# clocker-12b.net
KiCad netlist of a schematic drawn in EAGLE
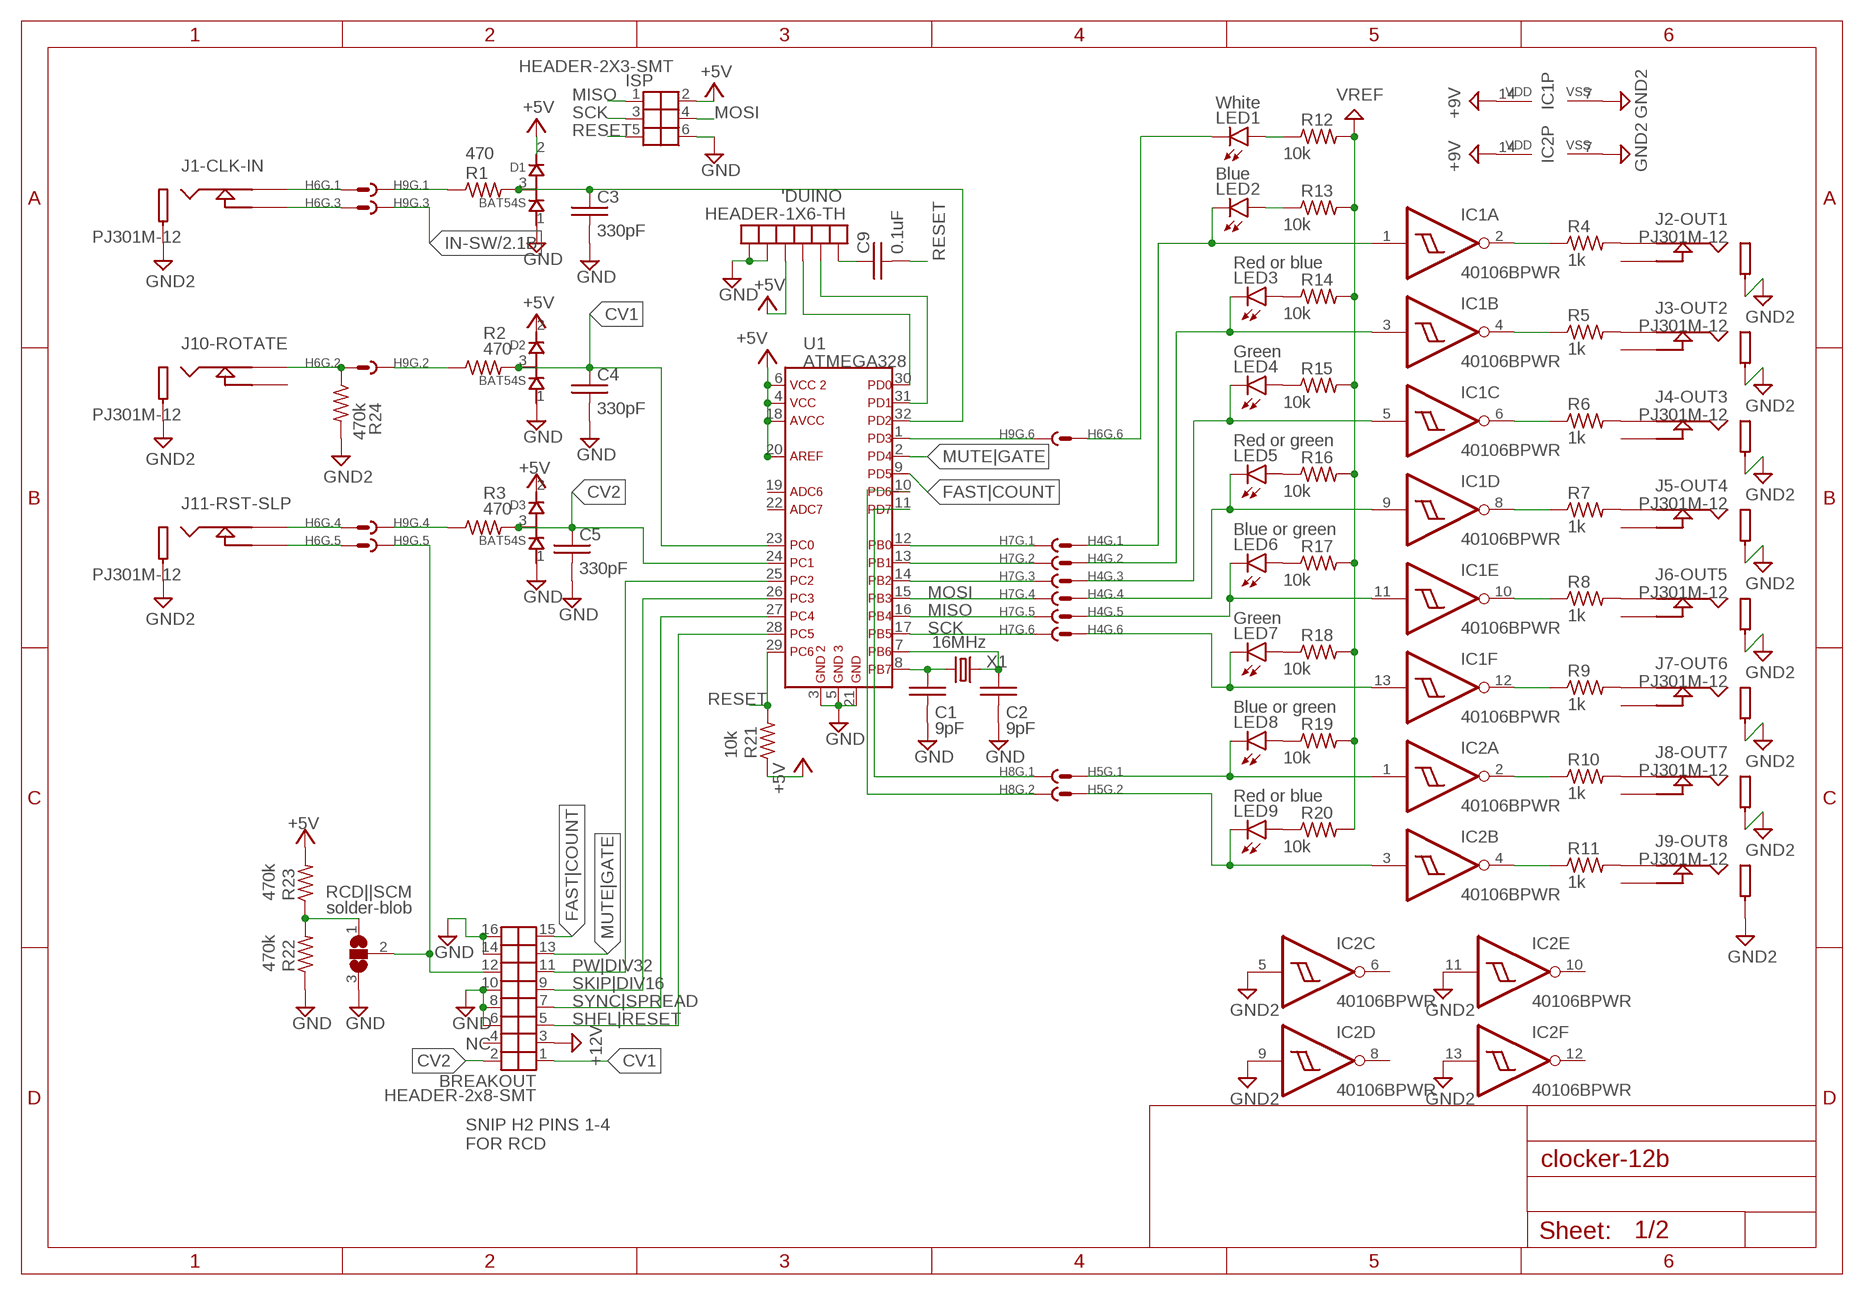
[diagram p0: schematic, sheet 1]
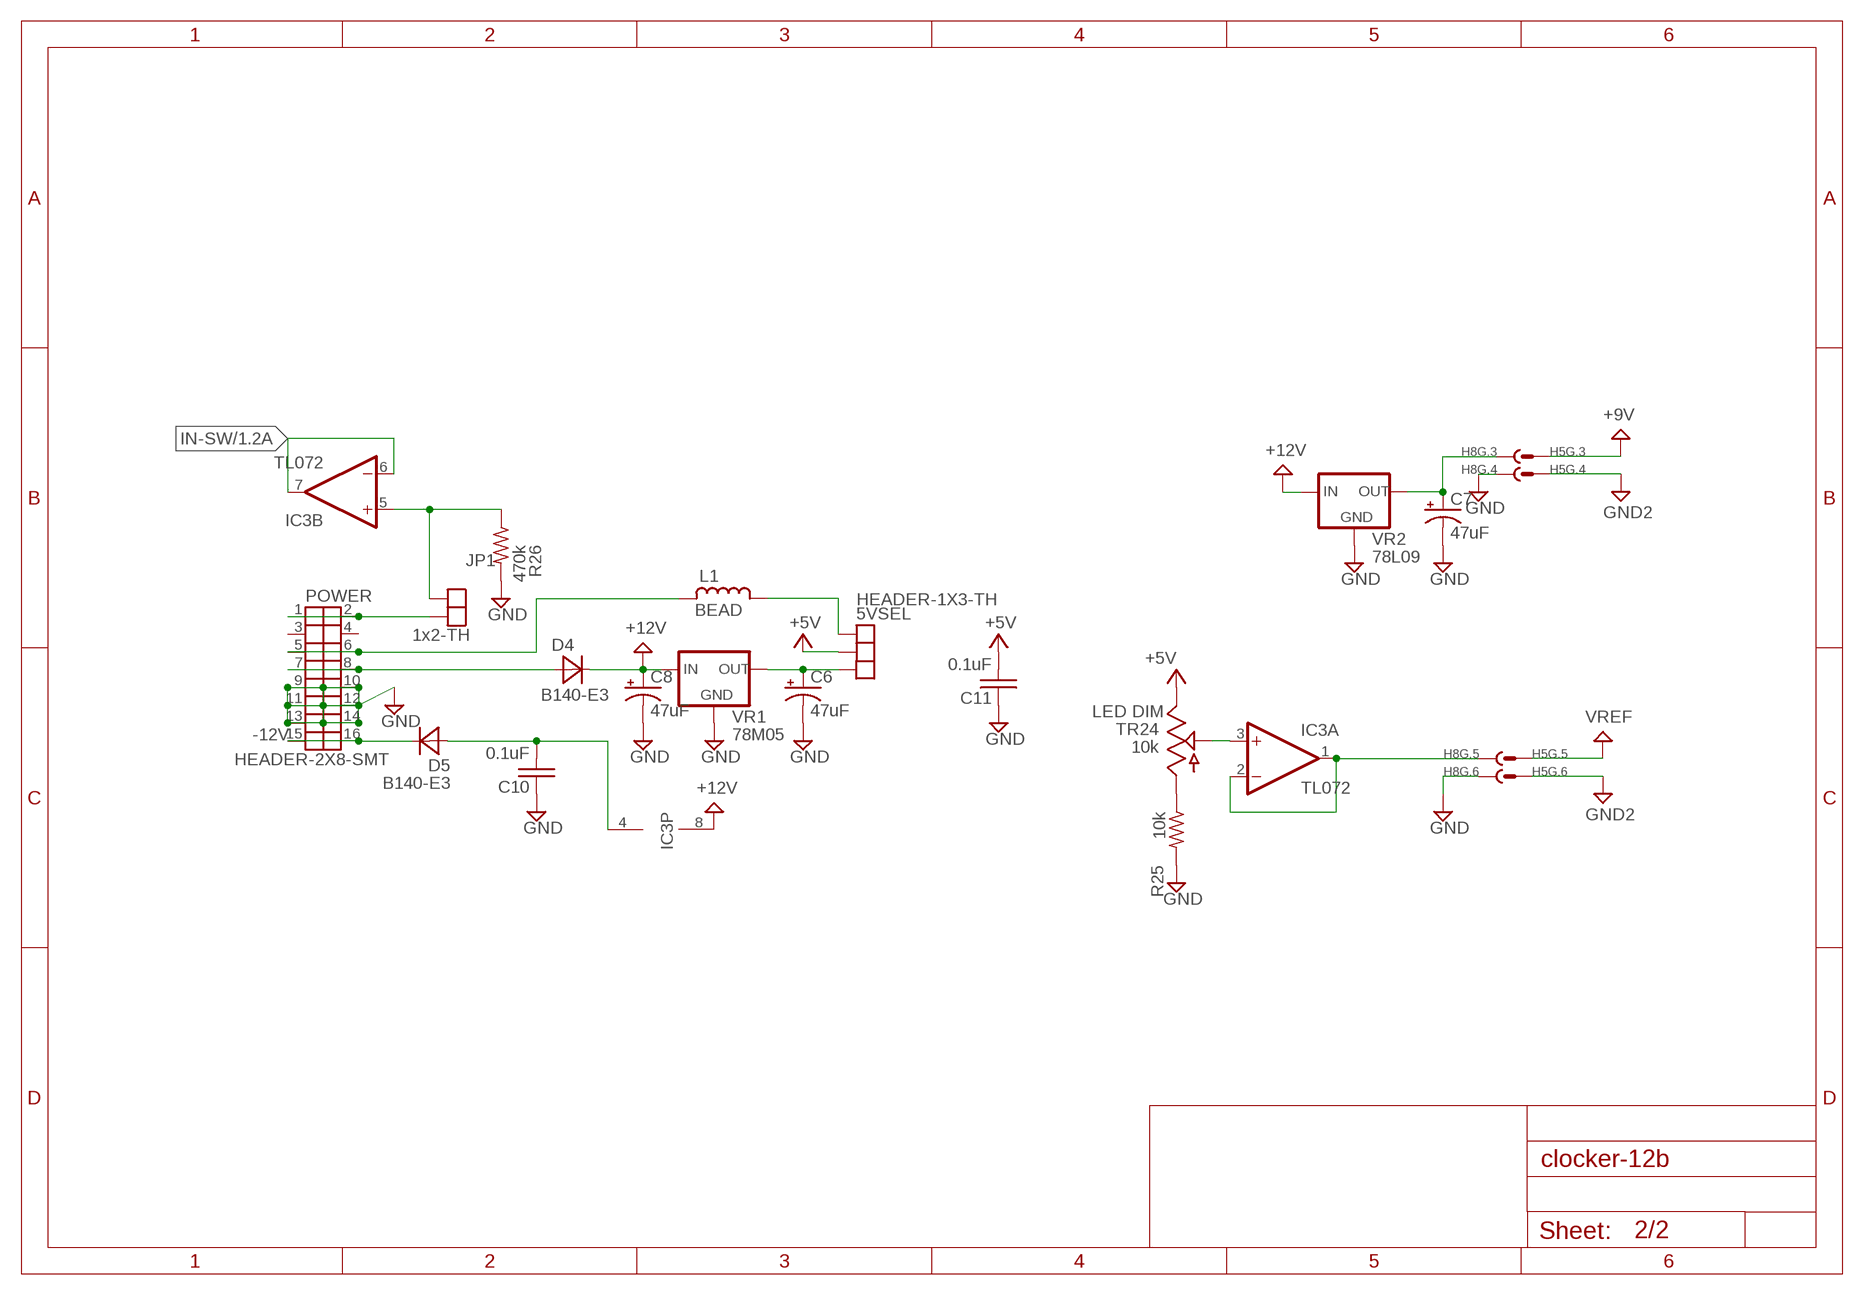
[diagram p1: schematic, sheet 2]

(export (version "E")
  (design (tool "Eeschema 10.0.6"))
  (components
    (comp (ref "5VSEL")
      (value "HEADER-1X3-TH")
      (footprint "eagle-import:HEADER-1X3-TH")
      (libsource (lib "eagle-import") (part "HEADER-1X3"))
    )
    (comp (ref "C6")
      (value "47uF")
      (footprint "eagle-import:C-POL-5")
      (libsource (lib "eagle-import") (part "C-POL5"))
    )
    (comp (ref "C7")
      (value "47uF")
      (footprint "eagle-import:C-POL-5")
      (libsource (lib "eagle-import") (part "C-POL5"))
    )
    (comp (ref "C8")
      (value "47uF")
      (footprint "eagle-import:C-POL-5")
      (libsource (lib "eagle-import") (part "C-POL5"))
    )
    (comp (ref "C10")
      (value "0.1uF")
      (footprint "eagle-import:C0603")
      (libsource (lib "eagle-import") (part "CB"))
    )
    (comp (ref "C11")
      (value "0.1uF")
      (footprint "eagle-import:C0603")
      (libsource (lib "eagle-import") (part "CB"))
    )
    (comp (ref "D4")
      (value "B140-E3")
      (footprint "eagle-import:SMA")
      (libsource (lib "eagle-import") (part "DA"))
    )
    (comp (ref "D5")
      (value "B140-E3")
      (footprint "eagle-import:SMA")
      (libsource (lib "eagle-import") (part "DA"))
    )
    (comp (ref "H5")
      (value "HEADER-2X3-B2B-MALESMT")
      (footprint "eagle-import:HEADER-2X3-SMT")
      (libsource (lib "eagle-import") (part "HEADER-2X3-B2B-MALESMT"))
    )
    (comp (ref "H8")
      (value "HEADER-2X3-B2B-FEMALETH-BOT")
      (footprint "eagle-import:HEADER-2X3-TH-BOTTOM")
      (libsource (lib "eagle-import") (part "HEADER-2X3-B2B-FEMALETH-BOT"))
    )
    (comp (ref "IC3")
      (value "TL072")
      (footprint "eagle-import:SOIC8")
      (libsource (lib "eagle-import") (part "OPAMP-2TL072M"))
    )
    (comp (ref "JP1")
      (value "1x2-TH")
      (footprint "eagle-import:HEADER-1X2-TH")
      (libsource (lib "eagle-import") (part "HEADER-1X2"))
    )
    (comp (ref "L1")
      (value "BEAD")
      (footprint "eagle-import:0603")
      (libsource (lib "eagle-import") (part "LB"))
    )
    (comp (ref "POWER")
      (value "HEADER-2X8-SMT")
      (footprint "eagle-import:HEADER-2X8-SMT-SHROUDED")
      (libsource (lib "eagle-import") (part "HEADER-2X8SHRD"))
    )
    (comp (ref "R25")
      (value "10k")
      (footprint "eagle-import:R0603")
      (libsource (lib "eagle-import") (part "RB"))
    )
    (comp (ref "R26")
      (value "470k")
      (footprint "eagle-import:R0603")
      (libsource (lib "eagle-import") (part "RB"))
    )
    (comp (ref "TR24")
      (value "10k")
      (footprint "eagle-import:PIHER-6MM")
      (fields (field (name "USE") "LED DIM"))
      (libsource (lib "eagle-import") (part "POT-MI"))
    )
    (comp (ref "VR1")
      (value "78M05")
      (footprint "eagle-import:DPAK")
      (libsource (lib "eagle-import") (part "VREG-POS78A"))
    )
    (comp (ref "VR2")
      (value "78L09")
      (footprint "eagle-import:SOT89")
      (libsource (lib "eagle-import") (part "VREG-POS78R"))
    )
    (comp (ref "'DUINO")
      (value "HEADER-1X6-TH")
      (footprint "eagle-import:HEADER-1X6-TH")
      (libsource (lib "eagle-import") (part "HEADER-1X6"))
    )
    (comp (ref "BREAKOUT")
      (value "HEADER-2x8-SMT")
      (footprint "eagle-import:HEADER-2X8-SMT")
      (libsource (lib "eagle-import") (part "HEADER-2X8BARE"))
    )
    (comp (ref "C1")
      (value "9pF")
      (footprint "eagle-import:C0603")
      (libsource (lib "eagle-import") (part "CB"))
    )
    (comp (ref "C2")
      (value "9pF")
      (footprint "eagle-import:C0603")
      (libsource (lib "eagle-import") (part "CB"))
    )
    (comp (ref "C3")
      (value "330pF")
      (footprint "eagle-import:C0603")
      (libsource (lib "eagle-import") (part "CB"))
    )
    (comp (ref "C4")
      (value "330pF")
      (footprint "eagle-import:C0603")
      (libsource (lib "eagle-import") (part "CB"))
    )
    (comp (ref "C5")
      (value "330pF")
      (footprint "eagle-import:C0603")
      (libsource (lib "eagle-import") (part "CB"))
    )
    (comp (ref "C9")
      (value "0.1uF")
      (footprint "eagle-import:C0603")
      (libsource (lib "eagle-import") (part "CB"))
    )
    (comp (ref "D1")
      (value "BAT54S")
      (footprint "eagle-import:SOT23")
      (libsource (lib "eagle-import") (part "DIODE-DUAL"))
    )
    (comp (ref "D2")
      (value "BAT54S")
      (footprint "eagle-import:SOT23")
      (libsource (lib "eagle-import") (part "DIODE-DUAL"))
    )
    (comp (ref "D3")
      (value "BAT54S")
      (footprint "eagle-import:SOT23")
      (libsource (lib "eagle-import") (part "DIODE-DUAL"))
    )
    (comp (ref "H4")
      (value "HEADER-2X3-B2B-MALESMT")
      (footprint "eagle-import:HEADER-2X3-SMT")
      (libsource (lib "eagle-import") (part "HEADER-2X3-B2B-MALESMT"))
    )
    (comp (ref "H6")
      (value "HEADER-2X3-B2B-MALESMT")
      (footprint "eagle-import:HEADER-2X3-SMT")
      (libsource (lib "eagle-import") (part "HEADER-2X3-B2B-MALESMT"))
    )
    (comp (ref "H7")
      (value "HEADER-2X3-B2B-FEMALETH-BOT")
      (footprint "eagle-import:HEADER-2X3-TH-BOTTOM")
      (libsource (lib "eagle-import") (part "HEADER-2X3-B2B-FEMALETH-BOT"))
    )
    (comp (ref "H9")
      (value "HEADER-2X3-B2B-FEMALETH-BOT")
      (footprint "eagle-import:HEADER-2X3-TH-BOTTOM")
      (libsource (lib "eagle-import") (part "HEADER-2X3-B2B-FEMALETH-BOT"))
    )
    (comp (ref "IC1")
      (value "40106BPWR")
      (footprint "eagle-import:TSSOP14")
      (libsource (lib "eagle-import") (part "40106BPWR"))
    )
    (comp (ref "IC2")
      (value "40106BPWR")
      (footprint "eagle-import:TSSOP14")
      (libsource (lib "eagle-import") (part "40106BPWR"))
    )
    (comp (ref "ISP")
      (value "HEADER-2X3-SMT")
      (footprint "eagle-import:HEADER-2X3-SMT")
      (libsource (lib "eagle-import") (part "HEADER-2X3"))
    )
    (comp (ref "J1-CLK-IN")
      (value "PJ301M-12")
      (footprint "eagle-import:PJ301M-12")
      (libsource (lib "eagle-import") (part "JACK-MONO-SWM"))
    )
    (comp (ref "J2-OUT1")
      (value "PJ301M-12")
      (footprint "eagle-import:PJ301M-12")
      (libsource (lib "eagle-import") (part "JACK-MONO-SWM"))
    )
    (comp (ref "J3-OUT2")
      (value "PJ301M-12")
      (footprint "eagle-import:PJ301M-12")
      (libsource (lib "eagle-import") (part "JACK-MONO-SWM"))
    )
    (comp (ref "J4-OUT3")
      (value "PJ301M-12")
      (footprint "eagle-import:PJ301M-12")
      (libsource (lib "eagle-import") (part "JACK-MONO-SWM"))
    )
    (comp (ref "J5-OUT4")
      (value "PJ301M-12")
      (footprint "eagle-import:PJ301M-12")
      (libsource (lib "eagle-import") (part "JACK-MONO-SWM"))
    )
    (comp (ref "J6-OUT5")
      (value "PJ301M-12")
      (footprint "eagle-import:PJ301M-12")
      (libsource (lib "eagle-import") (part "JACK-MONO-SWM"))
    )
    (comp (ref "J7-OUT6")
      (value "PJ301M-12")
      (footprint "eagle-import:PJ301M-12")
      (libsource (lib "eagle-import") (part "JACK-MONO-SWM"))
    )
    (comp (ref "J8-OUT7")
      (value "PJ301M-12")
      (footprint "eagle-import:PJ301M-12")
      (libsource (lib "eagle-import") (part "JACK-MONO-SWM"))
    )
    (comp (ref "J9-OUT8")
      (value "PJ301M-12")
      (footprint "eagle-import:PJ301M-12")
      (libsource (lib "eagle-import") (part "JACK-MONO-SWM"))
    )
    (comp (ref "J10-ROTATE")
      (value "PJ301M-12")
      (footprint "eagle-import:PJ301M-12")
      (libsource (lib "eagle-import") (part "JACK-MONO-SWM"))
    )
    (comp (ref "J11-RST-SLP")
      (value "PJ301M-12")
      (footprint "eagle-import:PJ301M-12")
      (libsource (lib "eagle-import") (part "JACK-MONO-SWM"))
    )
    (comp (ref "LED1")
      (value "White")
      (footprint "eagle-import:LED-T1")
      (libsource (lib "eagle-import") (part "LED"))
    )
    (comp (ref "LED2")
      (value "Blue")
      (footprint "eagle-import:LED-T1")
      (libsource (lib "eagle-import") (part "LED"))
    )
    (comp (ref "LED3")
      (value "Red or blue")
      (footprint "eagle-import:LED-T1")
      (libsource (lib "eagle-import") (part "LED"))
    )
    (comp (ref "LED4")
      (value "Green")
      (footprint "eagle-import:LED-T1")
      (libsource (lib "eagle-import") (part "LED"))
    )
    (comp (ref "LED5")
      (value "Red or green")
      (footprint "eagle-import:LED-T1")
      (libsource (lib "eagle-import") (part "LED"))
    )
    (comp (ref "LED6")
      (value "Blue or green")
      (footprint "eagle-import:LED-T1")
      (libsource (lib "eagle-import") (part "LED"))
    )
    (comp (ref "LED7")
      (value "Green")
      (footprint "eagle-import:LED-T1")
      (libsource (lib "eagle-import") (part "LED"))
    )
    (comp (ref "LED8")
      (value "Blue or green")
      (footprint "eagle-import:LED-T1")
      (libsource (lib "eagle-import") (part "LED"))
    )
    (comp (ref "LED9")
      (value "Red or blue")
      (footprint "eagle-import:LED-T1")
      (libsource (lib "eagle-import") (part "LED"))
    )
    (comp (ref "R1")
      (value "470")
      (footprint "eagle-import:R0603")
      (libsource (lib "eagle-import") (part "RB"))
    )
    (comp (ref "R2")
      (value "470")
      (footprint "eagle-import:R0603")
      (libsource (lib "eagle-import") (part "RB"))
    )
    (comp (ref "R3")
      (value "470")
      (footprint "eagle-import:R0603")
      (libsource (lib "eagle-import") (part "RB"))
    )
    (comp (ref "R4")
      (value "1k")
      (footprint "eagle-import:R0603")
      (libsource (lib "eagle-import") (part "RB"))
    )
    (comp (ref "R5")
      (value "1k")
      (footprint "eagle-import:R0603")
      (libsource (lib "eagle-import") (part "RB"))
    )
    (comp (ref "R6")
      (value "1k")
      (footprint "eagle-import:R0603")
      (libsource (lib "eagle-import") (part "RB"))
    )
    (comp (ref "R7")
      (value "1k")
      (footprint "eagle-import:R0603")
      (libsource (lib "eagle-import") (part "RB"))
    )
    (comp (ref "R8")
      (value "1k")
      (footprint "eagle-import:R0603")
      (libsource (lib "eagle-import") (part "RB"))
    )
    (comp (ref "R9")
      (value "1k")
      (footprint "eagle-import:R0603")
      (libsource (lib "eagle-import") (part "RB"))
    )
    (comp (ref "R10")
      (value "1k")
      (footprint "eagle-import:R0603")
      (libsource (lib "eagle-import") (part "RB"))
    )
    (comp (ref "R11")
      (value "1k")
      (footprint "eagle-import:R0603")
      (libsource (lib "eagle-import") (part "RB"))
    )
    (comp (ref "R12")
      (value "10k")
      (footprint "eagle-import:R0603")
      (libsource (lib "eagle-import") (part "RB"))
    )
    (comp (ref "R13")
      (value "10k")
      (footprint "eagle-import:R0603")
      (libsource (lib "eagle-import") (part "RB"))
    )
    (comp (ref "R14")
      (value "10k")
      (footprint "eagle-import:R0603")
      (libsource (lib "eagle-import") (part "RB"))
    )
    (comp (ref "R15")
      (value "10k")
      (footprint "eagle-import:R0603")
      (libsource (lib "eagle-import") (part "RB"))
    )
    (comp (ref "R16")
      (value "10k")
      (footprint "eagle-import:R0603")
      (libsource (lib "eagle-import") (part "RB"))
    )
    (comp (ref "R17")
      (value "10k")
      (footprint "eagle-import:R0603")
      (libsource (lib "eagle-import") (part "RB"))
    )
    (comp (ref "R18")
      (value "10k")
      (footprint "eagle-import:R0603")
      (libsource (lib "eagle-import") (part "RB"))
    )
    (comp (ref "R19")
      (value "10k")
      (footprint "eagle-import:R0603")
      (libsource (lib "eagle-import") (part "RB"))
    )
    (comp (ref "R20")
      (value "10k")
      (footprint "eagle-import:R0603")
      (libsource (lib "eagle-import") (part "RB"))
    )
    (comp (ref "R21")
      (value "10k")
      (footprint "eagle-import:R0603")
      (libsource (lib "eagle-import") (part "RB"))
    )
    (comp (ref "R22")
      (value "470k")
      (footprint "eagle-import:R0603")
      (libsource (lib "eagle-import") (part "RB"))
    )
    (comp (ref "R23")
      (value "470k")
      (footprint "eagle-import:R0603")
      (libsource (lib "eagle-import") (part "RB"))
    )
    (comp (ref "R24")
      (value "470k")
      (footprint "eagle-import:R0603")
      (libsource (lib "eagle-import") (part "RB"))
    )
    (comp (ref "RCD||SCM")
      (value "solder-blob")
      (footprint "eagle-import:SJ_2")
      (libsource (lib "eagle-import") (part "SJ2W"))
    )
    (comp (ref "U1")
      (value "ATMEGA328")
      (footprint "eagle-import:TQFP-32")
      (libsource (lib "eagle-import") (part "ATMEGA168"))
    )
    (comp (ref "X1")
      (value "16MHz")
      (footprint "eagle-import:FA-238")
      (libsource (lib "eagle-import") (part "CRYSTALE"))
    )
  )
  (nets
    (net (code "1") (name "+5V") (class "Default")
      (node (ref "'DUINO") (pin "P$3") (pinfunction "P$3_P$3") (pintype "bidirectional"))
      (node (ref "5VSEL") (pin "P$2") (pinfunction "P$2_P$2") (pintype "bidirectional"))
      (node (ref "C11") (pin "2") (pinfunction "2_2") (pintype "passive"))
      (node (ref "D1") (pin "2") (pinfunction "CATHODE_2") (pintype "bidirectional"))
      (node (ref "D2") (pin "2") (pinfunction "CATHODE_2") (pintype "bidirectional"))
      (node (ref "D3") (pin "2") (pinfunction "CATHODE_2") (pintype "bidirectional"))
      (node (ref "ISP") (pin "2") (pinfunction "P$2_2") (pintype "bidirectional"))
      (node (ref "R21") (pin "1") (pinfunction "1_1") (pintype "passive"))
      (node (ref "R23") (pin "2") (pinfunction "2_2") (pintype "passive"))
      (node (ref "TR24") (pin "3") (pinfunction "3_3") (pintype "passive"))
      (node (ref "U1") (pin "18") (pinfunction "P$18_18") (pintype "passive"))
      (node (ref "U1") (pin "20") (pinfunction "P$20_20") (pintype "passive"))
      (node (ref "U1") (pin "4") (pinfunction "P$4_4") (pintype "passive"))
      (node (ref "U1") (pin "6") (pinfunction "P$6_6") (pintype "passive"))
    )
    (net (code "2") (name "+9V") (class "Default")
      (node (ref "H5") (pin "3") (pinfunction "S_3") (pintype "passive"))
      (node (ref "IC1") (pin "14") (pinfunction "VDD_14") (pintype "power_in"))
      (node (ref "IC2") (pin "14") (pinfunction "VDD_14") (pintype "power_in"))
    )
    (net (code "3") (name "+12V") (class "Default")
      (node (ref "BREAKOUT") (pin "3") (pinfunction "P$3_3") (pintype "bidirectional"))
      (node (ref "C8") (pin "+") (pinfunction "+_+") (pintype "passive"))
      (node (ref "D4") (pin "K") (pinfunction "C_K") (pintype "passive"))
      (node (ref "IC3") (pin "8") (pinfunction "V+_8") (pintype "power_in"))
      (node (ref "VR1") (pin "1") (pinfunction "IN_1") (pintype "input"))
      (node (ref "VR2") (pin "3") (pinfunction "IN_3") (pintype "input"))
    )
    (net (code "4") (name "+VREF") (class "Default")
      (node (ref "H5") (pin "5") (pinfunction "S_5") (pintype "passive"))
      (node (ref "R12") (pin "2") (pinfunction "2_2") (pintype "passive"))
      (node (ref "R13") (pin "2") (pinfunction "2_2") (pintype "passive"))
      (node (ref "R14") (pin "2") (pinfunction "2_2") (pintype "passive"))
      (node (ref "R15") (pin "2") (pinfunction "2_2") (pintype "passive"))
      (node (ref "R16") (pin "2") (pinfunction "2_2") (pintype "passive"))
      (node (ref "R17") (pin "2") (pinfunction "2_2") (pintype "passive"))
      (node (ref "R18") (pin "2") (pinfunction "2_2") (pintype "passive"))
      (node (ref "R19") (pin "2") (pinfunction "2_2") (pintype "passive"))
      (node (ref "R20") (pin "2") (pinfunction "2_2") (pintype "passive"))
    )
    (net (code "5") (name "-12V") (class "Default")
      (node (ref "D5") (pin "K") (pinfunction "C_K") (pintype "passive"))
      (node (ref "POWER") (pin "15") (pinfunction "P$15_15") (pintype "bidirectional"))
      (node (ref "POWER") (pin "16") (pinfunction "P$16_16") (pintype "bidirectional"))
    )
    (net (code "6") (name "AGND") (class "Default")
      (node (ref "H5") (pin "4") (pinfunction "S_4") (pintype "passive"))
      (node (ref "H5") (pin "6") (pinfunction "S_6") (pintype "passive"))
      (node (ref "IC1") (pin "7") (pinfunction "VSS_7") (pintype "power_in"))
      (node (ref "IC2") (pin "11") (pinfunction "I_11") (pintype "input"))
      (node (ref "IC2") (pin "13") (pinfunction "I_13") (pintype "input"))
      (node (ref "IC2") (pin "5") (pinfunction "I_5") (pintype "input"))
      (node (ref "IC2") (pin "7") (pinfunction "VSS_7") (pintype "power_in"))
      (node (ref "IC2") (pin "9") (pinfunction "I_9") (pintype "input"))
      (node (ref "J1-CLK-IN") (pin "2") (pinfunction "SLEEVE_2") (pintype "passive"))
      (node (ref "J10-ROTATE") (pin "2") (pinfunction "SLEEVE_2") (pintype "passive"))
      (node (ref "J11-RST-SLP") (pin "2") (pinfunction "SLEEVE_2") (pintype "passive"))
      (node (ref "J2-OUT1") (pin "2") (pinfunction "SLEEVE_2") (pintype "passive"))
      (node (ref "J3-OUT2") (pin "2") (pinfunction "SLEEVE_2") (pintype "passive"))
      (node (ref "J4-OUT3") (pin "2") (pinfunction "SLEEVE_2") (pintype "passive"))
      (node (ref "J5-OUT4") (pin "2") (pinfunction "SLEEVE_2") (pintype "passive"))
      (node (ref "J6-OUT5") (pin "2") (pinfunction "SLEEVE_2") (pintype "passive"))
      (node (ref "J7-OUT6") (pin "2") (pinfunction "SLEEVE_2") (pintype "passive"))
      (node (ref "J8-OUT7") (pin "2") (pinfunction "SLEEVE_2") (pintype "passive"))
      (node (ref "J9-OUT8") (pin "2") (pinfunction "SLEEVE_2") (pintype "passive"))
      (node (ref "R24") (pin "2") (pinfunction "2_2") (pintype "passive"))
    )
    (net (code "7") (name "CV1") (class "Default")
      (node (ref "BREAKOUT") (pin "1") (pinfunction "P$1_1") (pintype "bidirectional"))
      (node (ref "C4") (pin "1") (pinfunction "1_1") (pintype "passive"))
      (node (ref "D2") (pin "3") (pinfunction "COMMON_3") (pintype "bidirectional"))
      (node (ref "R2") (pin "2") (pinfunction "2_2") (pintype "passive"))
      (node (ref "U1") (pin "23") (pinfunction "P$23_23") (pintype "passive"))
    )
    (net (code "8") (name "CV2") (class "Default")
      (node (ref "BREAKOUT") (pin "2") (pinfunction "P$2_2") (pintype "bidirectional"))
      (node (ref "C5") (pin "1") (pinfunction "1_1") (pintype "passive"))
      (node (ref "D3") (pin "3") (pinfunction "COMMON_3") (pintype "bidirectional"))
      (node (ref "R3") (pin "2") (pinfunction "2_2") (pintype "passive"))
      (node (ref "U1") (pin "24") (pinfunction "P$24_24") (pintype "passive"))
    )
    (net (code "9") (name "FAST|COUNT") (class "Default")
      (node (ref "BREAKOUT") (pin "15") (pinfunction "P$15_15") (pintype "bidirectional"))
      (node (ref "U1") (pin "9") (pinfunction "P$9_9") (pintype "passive"))
    )
    (net (code "10") (name "GND") (class "Default")
      (node (ref "'DUINO") (pin "P$1") (pinfunction "P$1_P$1") (pintype "bidirectional"))
      (node (ref "'DUINO") (pin "P$2") (pinfunction "P$2_P$2") (pintype "bidirectional"))
      (node (ref "BREAKOUT") (pin "10") (pinfunction "P$10_10") (pintype "bidirectional"))
      (node (ref "BREAKOUT") (pin "14") (pinfunction "P$14_14") (pintype "bidirectional"))
      (node (ref "BREAKOUT") (pin "16") (pinfunction "P$16_16") (pintype "bidirectional"))
      (node (ref "BREAKOUT") (pin "6") (pinfunction "P$6_6") (pintype "bidirectional"))
      (node (ref "BREAKOUT") (pin "8") (pinfunction "P$8_8") (pintype "bidirectional"))
      (node (ref "C1") (pin "2") (pinfunction "2_2") (pintype "passive"))
      (node (ref "C10") (pin "1") (pinfunction "1_1") (pintype "passive"))
      (node (ref "C11") (pin "1") (pinfunction "1_1") (pintype "passive"))
      (node (ref "C2") (pin "2") (pinfunction "2_2") (pintype "passive"))
      (node (ref "C3") (pin "2") (pinfunction "2_2") (pintype "passive"))
      (node (ref "C4") (pin "2") (pinfunction "2_2") (pintype "passive"))
      (node (ref "C5") (pin "2") (pinfunction "2_2") (pintype "passive"))
      (node (ref "C6") (pin "-") (pinfunction "-_-") (pintype "passive"))
      (node (ref "C7") (pin "-") (pinfunction "-_-") (pintype "passive"))
      (node (ref "C8") (pin "-") (pinfunction "-_-") (pintype "passive"))
      (node (ref "D1") (pin "1") (pinfunction "ANODE_1") (pintype "bidirectional"))
      (node (ref "D2") (pin "1") (pinfunction "ANODE_1") (pintype "bidirectional"))
      (node (ref "D3") (pin "1") (pinfunction "ANODE_1") (pintype "bidirectional"))
      (node (ref "H8") (pin "P$4") (pinfunction "B_P$4") (pintype "passive"))
      (node (ref "H8") (pin "P$6") (pinfunction "B_P$6") (pintype "passive"))
      (node (ref "ISP") (pin "6") (pinfunction "P$6_6") (pintype "bidirectional"))
      (node (ref "POWER") (pin "10") (pinfunction "P$10_10") (pintype "bidirectional"))
      (node (ref "POWER") (pin "11") (pinfunction "P$11_11") (pintype "bidirectional"))
      (node (ref "POWER") (pin "12") (pinfunction "P$12_12") (pintype "bidirectional"))
      (node (ref "POWER") (pin "13") (pinfunction "P$13_13") (pintype "bidirectional"))
      (node (ref "POWER") (pin "14") (pinfunction "P$14_14") (pintype "bidirectional"))
      (node (ref "POWER") (pin "9") (pinfunction "P$9_9") (pintype "bidirectional"))
      (node (ref "R22") (pin "1") (pinfunction "1_1") (pintype "passive"))
      (node (ref "R25") (pin "2") (pinfunction "2_2") (pintype "passive"))
      (node (ref "R26") (pin "2") (pinfunction "2_2") (pintype "passive"))
      (node (ref "RCD||SCM") (pin "3") (pinfunction "3_3") (pintype "passive"))
      (node (ref "U1") (pin "21") (pinfunction "P$21_21") (pintype "passive"))
      (node (ref "U1") (pin "3") (pinfunction "P$3_3") (pintype "passive"))
      (node (ref "U1") (pin "5") (pinfunction "P$5_5") (pintype "passive"))
      (node (ref "VR1") (pin "4") (pinfunction "GND_4") (pintype "input"))
      (node (ref "VR2") (pin "2A") (pinfunction "GND_2A") (pintype "input"))
      (node (ref "VR2") (pin "2B") (pinfunction "GND_2B") (pintype "input"))
    )
    (net (code "11") (name "IN-SW") (class "Default")
      (node (ref "H9") (pin "P$3") (pinfunction "B_P$3") (pintype "passive"))
      (node (ref "IC3") (pin "6") (pinfunction "-IN_6") (pintype "input"))
      (node (ref "IC3") (pin "7") (pinfunction "OUT_7") (pintype "output"))
    )
    (net (code "12") (name "MISO") (class "Default")
      (node (ref "H7") (pin "P$5") (pinfunction "B_P$5") (pintype "passive"))
      (node (ref "ISP") (pin "1") (pinfunction "P$1_1") (pintype "bidirectional"))
      (node (ref "U1") (pin "16") (pinfunction "P$16_16") (pintype "passive"))
    )
    (net (code "13") (name "MOSI") (class "Default")
      (node (ref "H7") (pin "P$4") (pinfunction "B_P$4") (pintype "passive"))
      (node (ref "ISP") (pin "4") (pinfunction "P$4_4") (pintype "bidirectional"))
      (node (ref "U1") (pin "15") (pinfunction "P$15_15") (pintype "passive"))
    )
    (net (code "14") (name "MUTE|GATE") (class "Default")
      (node (ref "BREAKOUT") (pin "13") (pinfunction "P$13_13") (pintype "bidirectional"))
      (node (ref "U1") (pin "2") (pinfunction "P$2_2") (pintype "passive"))
    )
    (net (code "15") (name "Net-('DUINO-PadP$6)") (class "Default")
      (node (ref "'DUINO") (pin "P$6") (pinfunction "P$6_P$6") (pintype "bidirectional"))
      (node (ref "C9") (pin "1") (pinfunction "1_1") (pintype "passive"))
    )
    (net (code "16") (name "Net-(BREAKOUT-P$12)") (class "Default")
      (node (ref "BREAKOUT") (pin "12") (pinfunction "P$12_12") (pintype "bidirectional"))
      (node (ref "H9") (pin "P$5") (pinfunction "B_P$5") (pintype "passive"))
      (node (ref "RCD||SCM") (pin "2") (pinfunction "2_2") (pintype "passive"))
    )
    (net (code "17") (name "Net-(D1-COMMON)") (class "Default")
      (node (ref "C3") (pin "1") (pinfunction "1_1") (pintype "passive"))
      (node (ref "D1") (pin "3") (pinfunction "COMMON_3") (pintype "bidirectional"))
      (node (ref "R1") (pin "2") (pinfunction "2_2") (pintype "passive"))
      (node (ref "U1") (pin "32") (pinfunction "P$32_32") (pintype "passive"))
    )
    (net (code "18") (name "Net-(H4A-S)") (class "Default")
      (node (ref "H4") (pin "1") (pinfunction "S_1") (pintype "passive"))
      (node (ref "IC1") (pin "1") (pinfunction "I_1") (pintype "input"))
      (node (ref "LED2") (pin "K") (pinfunction "C_K") (pintype "passive"))
    )
    (net (code "19") (name "Net-(H4B-S)") (class "Default")
      (node (ref "H4") (pin "2") (pinfunction "S_2") (pintype "passive"))
      (node (ref "IC1") (pin "3") (pinfunction "I_3") (pintype "input"))
      (node (ref "LED3") (pin "K") (pinfunction "C_K") (pintype "passive"))
    )
    (net (code "20") (name "Net-(H4C-S)") (class "Default")
      (node (ref "H4") (pin "3") (pinfunction "S_3") (pintype "passive"))
      (node (ref "IC1") (pin "5") (pinfunction "I_5") (pintype "input"))
      (node (ref "LED4") (pin "K") (pinfunction "C_K") (pintype "passive"))
    )
    (net (code "21") (name "Net-(H4D-S)") (class "Default")
      (node (ref "H4") (pin "4") (pinfunction "S_4") (pintype "passive"))
      (node (ref "IC1") (pin "9") (pinfunction "I_9") (pintype "input"))
      (node (ref "LED5") (pin "K") (pinfunction "C_K") (pintype "passive"))
    )
    (net (code "22") (name "Net-(H4E-S)") (class "Default")
      (node (ref "H4") (pin "5") (pinfunction "S_5") (pintype "passive"))
      (node (ref "IC1") (pin "11") (pinfunction "I_11") (pintype "input"))
      (node (ref "LED6") (pin "K") (pinfunction "C_K") (pintype "passive"))
    )
    (net (code "23") (name "Net-(H4F-S)") (class "Default")
      (node (ref "H4") (pin "6") (pinfunction "S_6") (pintype "passive"))
      (node (ref "IC1") (pin "13") (pinfunction "I_13") (pintype "input"))
      (node (ref "LED7") (pin "K") (pinfunction "C_K") (pintype "passive"))
    )
    (net (code "24") (name "Net-(H5A-S)") (class "Default")
      (node (ref "H5") (pin "1") (pinfunction "S_1") (pintype "passive"))
      (node (ref "IC2") (pin "1") (pinfunction "I_1") (pintype "input"))
      (node (ref "LED8") (pin "K") (pinfunction "C_K") (pintype "passive"))
    )
    (net (code "25") (name "Net-(H5B-S)") (class "Default")
      (node (ref "H5") (pin "2") (pinfunction "S_2") (pintype "passive"))
      (node (ref "IC2") (pin "3") (pinfunction "I_3") (pintype "input"))
      (node (ref "LED9") (pin "K") (pinfunction "C_K") (pintype "passive"))
    )
    (net (code "26") (name "Net-(H6A-S)") (class "Default")
      (node (ref "H6") (pin "1") (pinfunction "S_1") (pintype "passive"))
      (node (ref "J1-CLK-IN") (pin "1") (pinfunction "TIP_1") (pintype "passive"))
    )
    (net (code "27") (name "Net-(H6B-S)") (class "Default")
      (node (ref "H6") (pin "2") (pinfunction "S_2") (pintype "passive"))
      (node (ref "J10-ROTATE") (pin "1") (pinfunction "TIP_1") (pintype "passive"))
      (node (ref "R24") (pin "1") (pinfunction "1_1") (pintype "passive"))
    )
    (net (code "28") (name "Net-(H6C-S)") (class "Default")
      (node (ref "H6") (pin "3") (pinfunction "S_3") (pintype "passive"))
      (node (ref "J1-CLK-IN") (pin "3") (pinfunction "TIP-SW_3") (pintype "passive"))
    )
    (net (code "29") (name "Net-(H6D-S)") (class "Default")
      (node (ref "H6") (pin "4") (pinfunction "S_4") (pintype "passive"))
      (node (ref "J11-RST-SLP") (pin "1") (pinfunction "TIP_1") (pintype "passive"))
    )
    (net (code "30") (name "Net-(H6E-S)") (class "Default")
      (node (ref "H6") (pin "5") (pinfunction "S_5") (pintype "passive"))
      (node (ref "J11-RST-SLP") (pin "3") (pinfunction "TIP-SW_3") (pintype "passive"))
    )
    (net (code "31") (name "Net-(H6F-S)") (class "Default")
      (node (ref "H6") (pin "6") (pinfunction "S_6") (pintype "passive"))
      (node (ref "LED1") (pin "K") (pinfunction "C_K") (pintype "passive"))
    )
    (net (code "32") (name "Net-(H7A-B)") (class "Default")
      (node (ref "H7") (pin "P$1") (pinfunction "B_P$1") (pintype "passive"))
      (node (ref "U1") (pin "12") (pinfunction "P$12_12") (pintype "passive"))
    )
    (net (code "33") (name "Net-(H7B-B)") (class "Default")
      (node (ref "H7") (pin "P$2") (pinfunction "B_P$2") (pintype "passive"))
      (node (ref "U1") (pin "13") (pinfunction "P$13_13") (pintype "passive"))
    )
    (net (code "34") (name "Net-(H7C-B)") (class "Default")
      (node (ref "H7") (pin "P$3") (pinfunction "B_P$3") (pintype "passive"))
      (node (ref "U1") (pin "14") (pinfunction "P$14_14") (pintype "passive"))
    )
    (net (code "35") (name "Net-(H8A-B)") (class "Default")
      (node (ref "H8") (pin "P$1") (pinfunction "B_P$1") (pintype "passive"))
      (node (ref "U1") (pin "11") (pinfunction "P$11_11") (pintype "passive"))
    )
    (net (code "36") (name "Net-(H8B-B)") (class "Default")
      (node (ref "H8") (pin "P$2") (pinfunction "B_P$2") (pintype "passive"))
      (node (ref "U1") (pin "10") (pinfunction "P$10_10") (pintype "passive"))
    )
    (net (code "37") (name "Net-(H8C-B)") (class "Default")
      (node (ref "C7") (pin "+") (pinfunction "+_+") (pintype "passive"))
      (node (ref "H8") (pin "P$3") (pinfunction "B_P$3") (pintype "passive"))
      (node (ref "VR2") (pin "1") (pinfunction "OUT_1") (pintype "passive"))
    )
    (net (code "38") (name "Net-(H8E-B)") (class "Default")
      (node (ref "H8") (pin "P$5") (pinfunction "B_P$5") (pintype "passive"))
      (node (ref "IC3") (pin "1") (pinfunction "OUT_1") (pintype "output"))
      (node (ref "IC3") (pin "2") (pinfunction "-IN_2") (pintype "input"))
    )
    (net (code "39") (name "Net-(H9A-B)") (class "Default")
      (node (ref "H9") (pin "P$1") (pinfunction "B_P$1") (pintype "passive"))
      (node (ref "R1") (pin "1") (pinfunction "1_1") (pintype "passive"))
    )
    (net (code "40") (name "Net-(H9B-B)") (class "Default")
      (node (ref "H9") (pin "P$2") (pinfunction "B_P$2") (pintype "passive"))
      (node (ref "R2") (pin "1") (pinfunction "1_1") (pintype "passive"))
    )
    (net (code "41") (name "Net-(H9D-B)") (class "Default")
      (node (ref "H9") (pin "P$4") (pinfunction "B_P$4") (pintype "passive"))
      (node (ref "R3") (pin "1") (pinfunction "1_1") (pintype "passive"))
    )
    (net (code "42") (name "Net-(H9F-B)") (class "Default")
      (node (ref "H9") (pin "P$6") (pinfunction "B_P$6") (pintype "passive"))
      (node (ref "U1") (pin "1") (pinfunction "P$1_1") (pintype "passive"))
    )
    (net (code "43") (name "Net-(IC1A-O)") (class "Default")
      (node (ref "IC1") (pin "2") (pinfunction "O_2") (pintype "output"))
      (node (ref "R4") (pin "1") (pinfunction "1_1") (pintype "passive"))
    )
    (net (code "44") (name "Net-(IC1B-O)") (class "Default")
      (node (ref "IC1") (pin "4") (pinfunction "O_4") (pintype "output"))
      (node (ref "R5") (pin "1") (pinfunction "1_1") (pintype "passive"))
    )
    (net (code "45") (name "Net-(IC1C-O)") (class "Default")
      (node (ref "IC1") (pin "6") (pinfunction "O_6") (pintype "output"))
      (node (ref "R6") (pin "1") (pinfunction "1_1") (pintype "passive"))
    )
    (net (code "46") (name "Net-(IC1D-O)") (class "Default")
      (node (ref "IC1") (pin "8") (pinfunction "O_8") (pintype "output"))
      (node (ref "R7") (pin "1") (pinfunction "1_1") (pintype "passive"))
    )
    (net (code "47") (name "Net-(IC1E-O)") (class "Default")
      (node (ref "IC1") (pin "10") (pinfunction "O_10") (pintype "output"))
      (node (ref "R8") (pin "1") (pinfunction "1_1") (pintype "passive"))
    )
    (net (code "48") (name "Net-(IC1F-O)") (class "Default")
      (node (ref "IC1") (pin "12") (pinfunction "O_12") (pintype "output"))
      (node (ref "R9") (pin "1") (pinfunction "1_1") (pintype "passive"))
    )
    (net (code "49") (name "Net-(IC2A-O)") (class "Default")
      (node (ref "IC2") (pin "2") (pinfunction "O_2") (pintype "output"))
      (node (ref "R10") (pin "1") (pinfunction "1_1") (pintype "passive"))
    )
    (net (code "50") (name "Net-(IC2B-O)") (class "Default")
      (node (ref "IC2") (pin "4") (pinfunction "O_4") (pintype "output"))
      (node (ref "R11") (pin "1") (pinfunction "1_1") (pintype "passive"))
    )
    (net (code "51") (name "Net-(IC3A-+IN)") (class "Default")
      (node (ref "IC3") (pin "3") (pinfunction "+IN_3") (pintype "input"))
      (node (ref "TR24") (pin "2") (pinfunction "2_2") (pintype "passive"))
    )
    (net (code "52") (name "Net-(IC3B-+IN)") (class "Default")
      (node (ref "IC3") (pin "5") (pinfunction "+IN_5") (pintype "input"))
      (node (ref "JP1") (pin "P$1") (pinfunction "P$1_P$1") (pintype "bidirectional"))
      (node (ref "R26") (pin "1") (pinfunction "1_1") (pintype "passive"))
    )
    (net (code "53") (name "Net-(IC3C-V-)") (class "Default")
      (node (ref "C10") (pin "2") (pinfunction "2_2") (pintype "passive"))
      (node (ref "D5") (pin "A") (pinfunction "A_A") (pintype "passive"))
      (node (ref "IC3") (pin "4") (pinfunction "V-_4") (pintype "power_in"))
    )
    (net (code "54") (name "Net-(J2-OUT1-TIP)") (class "Default")
      (node (ref "J2-OUT1") (pin "1") (pinfunction "TIP_1") (pintype "passive"))
      (node (ref "R4") (pin "2") (pinfunction "2_2") (pintype "passive"))
    )
    (net (code "55") (name "Net-(J3-OUT2-TIP)") (class "Default")
      (node (ref "J3-OUT2") (pin "1") (pinfunction "TIP_1") (pintype "passive"))
      (node (ref "R5") (pin "2") (pinfunction "2_2") (pintype "passive"))
    )
    (net (code "56") (name "Net-(J4-OUT3-TIP)") (class "Default")
      (node (ref "J4-OUT3") (pin "1") (pinfunction "TIP_1") (pintype "passive"))
      (node (ref "R6") (pin "2") (pinfunction "2_2") (pintype "passive"))
    )
    (net (code "57") (name "Net-(J5-OUT4-TIP)") (class "Default")
      (node (ref "J5-OUT4") (pin "1") (pinfunction "TIP_1") (pintype "passive"))
      (node (ref "R7") (pin "2") (pinfunction "2_2") (pintype "passive"))
    )
    (net (code "58") (name "Net-(J6-OUT5-TIP)") (class "Default")
      (node (ref "J6-OUT5") (pin "1") (pinfunction "TIP_1") (pintype "passive"))
      (node (ref "R8") (pin "2") (pinfunction "2_2") (pintype "passive"))
    )
    (net (code "59") (name "Net-(J7-OUT6-TIP)") (class "Default")
      (node (ref "J7-OUT6") (pin "1") (pinfunction "TIP_1") (pintype "passive"))
      (node (ref "R9") (pin "2") (pinfunction "2_2") (pintype "passive"))
    )
    (net (code "60") (name "Net-(J8-OUT7-TIP)") (class "Default")
      (node (ref "J8-OUT7") (pin "1") (pinfunction "TIP_1") (pintype "passive"))
      (node (ref "R10") (pin "2") (pinfunction "2_2") (pintype "passive"))
    )
    (net (code "61") (name "Net-(J9-OUT8-TIP)") (class "Default")
      (node (ref "J9-OUT8") (pin "1") (pinfunction "TIP_1") (pintype "passive"))
      (node (ref "R11") (pin "2") (pinfunction "2_2") (pintype "passive"))
    )
    (net (code "62") (name "Net-(L1-4)") (class "Default")
      (node (ref "5VSEL") (pin "P$1") (pinfunction "P$1_P$1") (pintype "bidirectional"))
      (node (ref "L1") (pin "2") (pinfunction "4_2") (pintype "passive"))
    )
    (net (code "63") (name "Net-(LED1-PadA)") (class "Default")
      (node (ref "LED1") (pin "A") (pinfunction "A_A") (pintype "passive"))
      (node (ref "R12") (pin "1") (pinfunction "1_1") (pintype "passive"))
    )
    (net (code "64") (name "Net-(LED2-PadA)") (class "Default")
      (node (ref "LED2") (pin "A") (pinfunction "A_A") (pintype "passive"))
      (node (ref "R13") (pin "1") (pinfunction "1_1") (pintype "passive"))
    )
    (net (code "65") (name "Net-(LED3-PadA)") (class "Default")
      (node (ref "LED3") (pin "A") (pinfunction "A_A") (pintype "passive"))
      (node (ref "R14") (pin "1") (pinfunction "1_1") (pintype "passive"))
    )
    (net (code "66") (name "Net-(LED4-PadA)") (class "Default")
      (node (ref "LED4") (pin "A") (pinfunction "A_A") (pintype "passive"))
      (node (ref "R15") (pin "1") (pinfunction "1_1") (pintype "passive"))
    )
    (net (code "67") (name "Net-(LED5-PadA)") (class "Default")
      (node (ref "LED5") (pin "A") (pinfunction "A_A") (pintype "passive"))
      (node (ref "R16") (pin "1") (pinfunction "1_1") (pintype "passive"))
    )
    (net (code "68") (name "Net-(LED6-PadA)") (class "Default")
      (node (ref "LED6") (pin "A") (pinfunction "A_A") (pintype "passive"))
      (node (ref "R17") (pin "1") (pinfunction "1_1") (pintype "passive"))
    )
    (net (code "69") (name "Net-(LED7-PadA)") (class "Default")
      (node (ref "LED7") (pin "A") (pinfunction "A_A") (pintype "passive"))
      (node (ref "R18") (pin "1") (pinfunction "1_1") (pintype "passive"))
    )
    (net (code "70") (name "Net-(LED8-PadA)") (class "Default")
      (node (ref "LED8") (pin "A") (pinfunction "A_A") (pintype "passive"))
      (node (ref "R19") (pin "1") (pinfunction "1_1") (pintype "passive"))
    )
    (net (code "71") (name "Net-(LED9-PadA)") (class "Default")
      (node (ref "LED9") (pin "A") (pinfunction "A_A") (pintype "passive"))
      (node (ref "R20") (pin "1") (pinfunction "1_1") (pintype "passive"))
    )
    (net (code "72") (name "Net-(POWER-P$1)") (class "Default")
      (node (ref "JP1") (pin "P$2") (pinfunction "P$2_P$2") (pintype "bidirectional"))
      (node (ref "POWER") (pin "1") (pinfunction "P$1_1") (pintype "bidirectional"))
      (node (ref "POWER") (pin "2") (pinfunction "P$2_2") (pintype "bidirectional"))
    )
    (net (code "73") (name "Net-(POWER-P$5)") (class "Default")
      (node (ref "L1") (pin "1") (pinfunction "1_1") (pintype "passive"))
      (node (ref "POWER") (pin "5") (pinfunction "P$5_5") (pintype "bidirectional"))
      (node (ref "POWER") (pin "6") (pinfunction "P$6_6") (pintype "bidirectional"))
    )
    (net (code "74") (name "Net-(POWER-P$7)") (class "Default")
      (node (ref "D4") (pin "A") (pinfunction "A_A") (pintype "passive"))
      (node (ref "POWER") (pin "7") (pinfunction "P$7_7") (pintype "bidirectional"))
      (node (ref "POWER") (pin "8") (pinfunction "P$8_8") (pintype "bidirectional"))
    )
    (net (code "75") (name "Net-(R22-Pad2)") (class "Default")
      (node (ref "R22") (pin "2") (pinfunction "2_2") (pintype "passive"))
      (node (ref "R23") (pin "1") (pinfunction "1_1") (pintype "passive"))
      (node (ref "RCD||SCM") (pin "1") (pinfunction "1_1") (pintype "passive"))
    )
    (net (code "76") (name "Net-(R25-Pad1)") (class "Default")
      (node (ref "R25") (pin "1") (pinfunction "1_1") (pintype "passive"))
      (node (ref "TR24") (pin "1") (pinfunction "1_1") (pintype "passive"))
    )
    (net (code "77") (name "Net-(U1-P$7)") (class "Default")
      (node (ref "C2") (pin "1") (pinfunction "1_1") (pintype "passive"))
      (node (ref "U1") (pin "7") (pinfunction "P$7_7") (pintype "passive"))
      (node (ref "X1") (pin "1") (pinfunction "1_1") (pintype "passive"))
    )
    (net (code "78") (name "Net-(U1-P$8)") (class "Default")
      (node (ref "C1") (pin "1") (pinfunction "1_1") (pintype "passive"))
      (node (ref "U1") (pin "8") (pinfunction "P$8_8") (pintype "passive"))
      (node (ref "X1") (pin "3") (pinfunction "2_3") (pintype "passive"))
    )
    (net (code "79") (name "Net-(U1-P$30)") (class "Default")
      (node (ref "'DUINO") (pin "P$4") (pinfunction "P$4_P$4") (pintype "bidirectional"))
      (node (ref "U1") (pin "30") (pinfunction "P$30_30") (pintype "passive"))
    )
    (net (code "80") (name "Net-(U1-P$31)") (class "Default")
      (node (ref "'DUINO") (pin "P$5") (pinfunction "P$5_P$5") (pintype "bidirectional"))
      (node (ref "U1") (pin "31") (pinfunction "P$31_31") (pintype "passive"))
    )
    (net (code "81") (name "Net-(VR1-OUT)") (class "Default")
      (node (ref "5VSEL") (pin "P$3") (pinfunction "P$3_P$3") (pintype "bidirectional"))
      (node (ref "C6") (pin "+") (pinfunction "+_+") (pintype "passive"))
      (node (ref "VR1") (pin "3") (pinfunction "OUT_3") (pintype "passive"))
    )
    (net (code "82") (name "PW|DIV32") (class "Default")
      (node (ref "BREAKOUT") (pin "11") (pinfunction "P$11_11") (pintype "bidirectional"))
      (node (ref "U1") (pin "25") (pinfunction "P$25_25") (pintype "passive"))
    )
    (net (code "83") (name "RESET") (class "Default")
      (node (ref "C9") (pin "2") (pinfunction "2_2") (pintype "passive"))
      (node (ref "ISP") (pin "5") (pinfunction "P$5_5") (pintype "bidirectional"))
      (node (ref "R21") (pin "2") (pinfunction "2_2") (pintype "passive"))
      (node (ref "U1") (pin "29") (pinfunction "P$29_29") (pintype "passive"))
    )
    (net (code "84") (name "SCK") (class "Default")
      (node (ref "H7") (pin "P$6") (pinfunction "B_P$6") (pintype "passive"))
      (node (ref "ISP") (pin "3") (pinfunction "P$3_3") (pintype "bidirectional"))
      (node (ref "U1") (pin "17") (pinfunction "P$17_17") (pintype "passive"))
    )
    (net (code "85") (name "SHFL|RESET") (class "Default")
      (node (ref "BREAKOUT") (pin "5") (pinfunction "P$5_5") (pintype "bidirectional"))
      (node (ref "U1") (pin "28") (pinfunction "P$28_28") (pintype "passive"))
    )
    (net (code "86") (name "SKIP|DIV16") (class "Default")
      (node (ref "BREAKOUT") (pin "9") (pinfunction "P$9_9") (pintype "bidirectional"))
      (node (ref "U1") (pin "26") (pinfunction "P$26_26") (pintype "passive"))
    )
    (net (code "87") (name "SYNC|SPREAD") (class "Default")
      (node (ref "BREAKOUT") (pin "7") (pinfunction "P$7_7") (pintype "bidirectional"))
      (node (ref "U1") (pin "27") (pinfunction "P$27_27") (pintype "passive"))
    )
    (net (code "88") (name "unconnected-(BREAKOUT-P$4-Pad4)") (class "Default")
      (node (ref "BREAKOUT") (pin "4") (pinfunction "P$4_4") (pintype "bidirectional"))
    )
    (net (code "89") (name "unconnected-(IC2C-O-Pad6)") (class "Default")
      (node (ref "IC2") (pin "6") (pinfunction "O_6") (pintype "output"))
    )
    (net (code "90") (name "unconnected-(IC2D-O-Pad8)") (class "Default")
      (node (ref "IC2") (pin "8") (pinfunction "O_8") (pintype "output"))
    )
    (net (code "91") (name "unconnected-(IC2E-O-Pad10)") (class "Default")
      (node (ref "IC2") (pin "10") (pinfunction "O_10") (pintype "output"))
    )
    (net (code "92") (name "unconnected-(IC2F-O-Pad12)") (class "Default")
      (node (ref "IC2") (pin "12") (pinfunction "O_12") (pintype "output"))
    )
    (net (code "93") (name "unconnected-(J2-OUT1-TIP-SW-Pad3)") (class "Default")
      (node (ref "J2-OUT1") (pin "3") (pinfunction "TIP-SW_3") (pintype "passive"))
    )
    (net (code "94") (name "unconnected-(J3-OUT2-TIP-SW-Pad3)") (class "Default")
      (node (ref "J3-OUT2") (pin "3") (pinfunction "TIP-SW_3") (pintype "passive"))
    )
    (net (code "95") (name "unconnected-(J4-OUT3-TIP-SW-Pad3)") (class "Default")
      (node (ref "J4-OUT3") (pin "3") (pinfunction "TIP-SW_3") (pintype "passive"))
    )
    (net (code "96") (name "unconnected-(J5-OUT4-TIP-SW-Pad3)") (class "Default")
      (node (ref "J5-OUT4") (pin "3") (pinfunction "TIP-SW_3") (pintype "passive"))
    )
    (net (code "97") (name "unconnected-(J6-OUT5-TIP-SW-Pad3)") (class "Default")
      (node (ref "J6-OUT5") (pin "3") (pinfunction "TIP-SW_3") (pintype "passive"))
    )
    (net (code "98") (name "unconnected-(J7-OUT6-TIP-SW-Pad3)") (class "Default")
      (node (ref "J7-OUT6") (pin "3") (pinfunction "TIP-SW_3") (pintype "passive"))
    )
    (net (code "99") (name "unconnected-(J8-OUT7-TIP-SW-Pad3)") (class "Default")
      (node (ref "J8-OUT7") (pin "3") (pinfunction "TIP-SW_3") (pintype "passive"))
    )
    (net (code "100") (name "unconnected-(J9-OUT8-TIP-SW-Pad3)") (class "Default")
      (node (ref "J9-OUT8") (pin "3") (pinfunction "TIP-SW_3") (pintype "passive"))
    )
    (net (code "101") (name "unconnected-(J10-ROTATE-TIP-SW-Pad3)") (class "Default")
      (node (ref "J10-ROTATE") (pin "3") (pinfunction "TIP-SW_3") (pintype "passive"))
    )
    (net (code "102") (name "unconnected-(POWER-P$3-Pad3)") (class "Default")
      (node (ref "POWER") (pin "3") (pinfunction "P$3_3") (pintype "bidirectional"))
    )
    (net (code "103") (name "unconnected-(POWER-P$4-Pad4)") (class "Default")
      (node (ref "POWER") (pin "4") (pinfunction "P$4_4") (pintype "bidirectional"))
    )
    (net (code "104") (name "unconnected-(U1-P$19-Pad19)") (class "Default")
      (node (ref "U1") (pin "19") (pinfunction "P$19_19") (pintype "passive"))
    )
    (net (code "105") (name "unconnected-(U1-P$22-Pad22)") (class "Default")
      (node (ref "U1") (pin "22") (pinfunction "P$22_22") (pintype "passive"))
    )
  )
)
